# Motor_Driver_SCH_1.net
KiCad netlist of a schematic drawn in Altium Designer
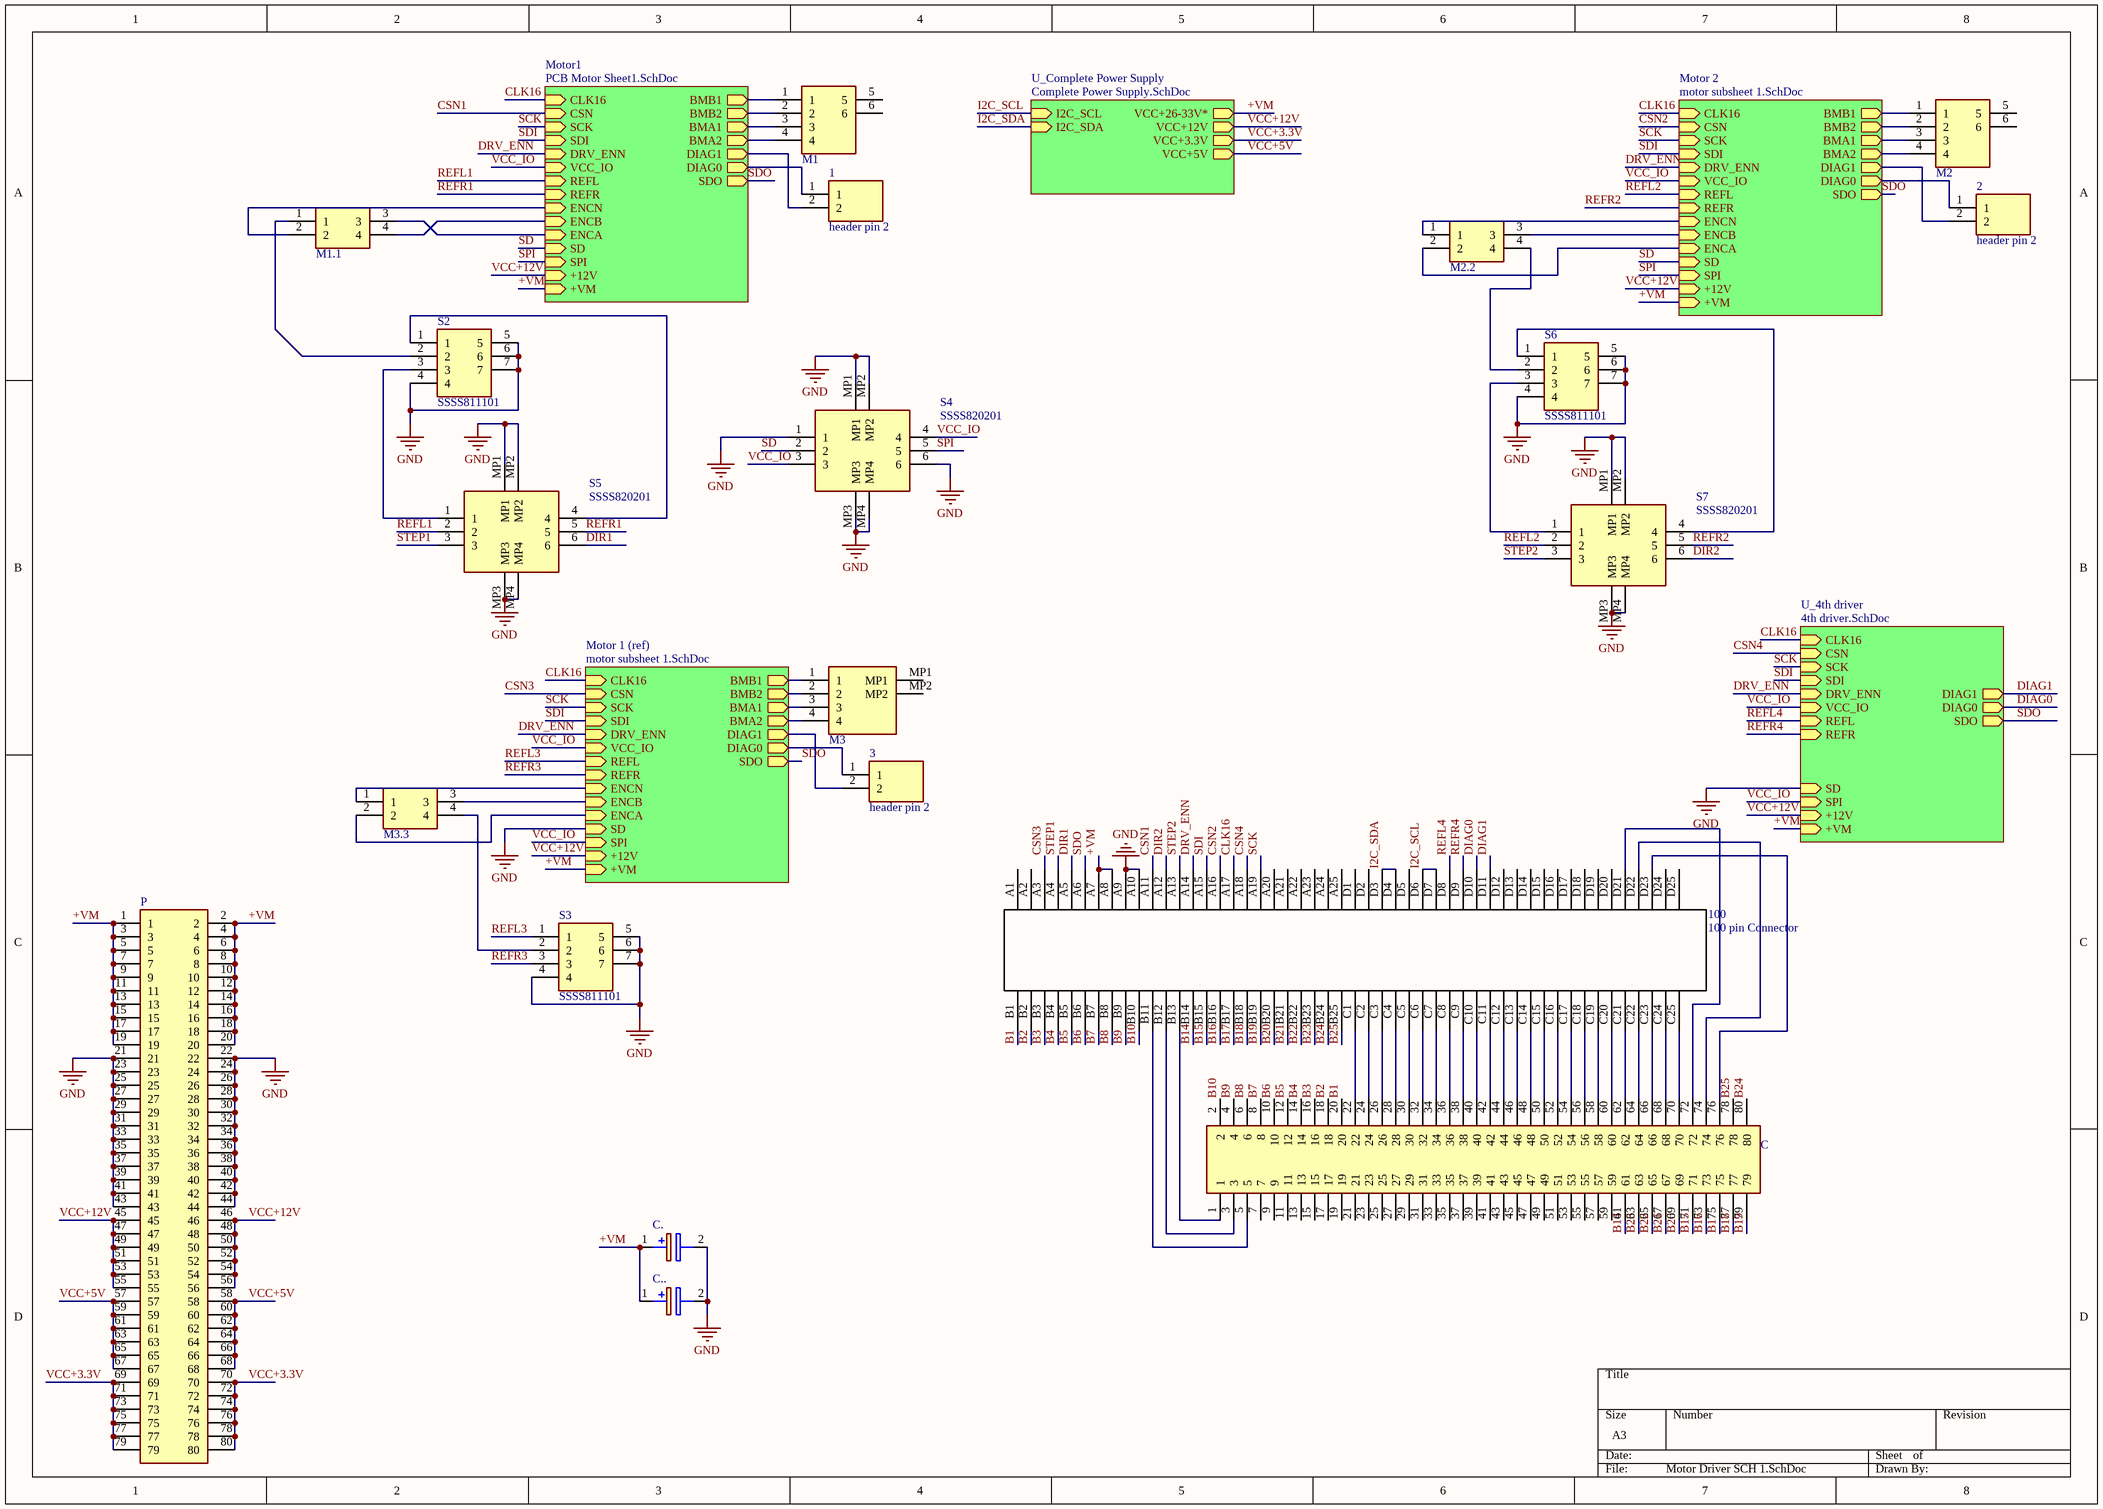
[diagram p0: Motor Driver SCH 1.SchDoc]

(export (version "E")
  (design (tool "Eeschema 10.0.6"))
  (components
    (comp (ref "1")
      (value "header pin 2")
      (footprint "2 pin header")
      (libsource (lib "SamacSys") (part "header pin 2"))
    )
    (comp (ref "2")
      (value "header pin 2")
      (footprint "2 pin header")
      (libsource (lib "SamacSys") (part "header pin 2"))
    )
    (comp (ref "3")
      (value "header pin 2")
      (footprint "2 pin header")
      (libsource (lib "SamacSys") (part "header pin 2"))
    )
    (comp (ref "100")
      (value "100 pin Connector")
      (footprint "SAMTEC_FOLC-125-M1-L-Q-LC")
      (libsource (lib "100 PIN Schlib1") (part "100 pin Connector"))
    )
    (comp (ref "C")
      (value "5-5179180-3")
      (footprint "SamacSys:551791803")
      (description "Connector")
      (fields (field (name "MOUSER PART NUMBER") "571-5-5179180-3"))
      (libsource (lib "") (part "5-5179180-3_1"))
    )
    (comp (ref "C.")
      (value "TPSD476M035R0300V")
      (footprint "SamacSys:CAPPM7344X310N")
      (description "Capacitor Polarised")
      (fields (field (name "MOUSER PART NUMBER") "581-TPSD476M035R300V"))
      (libsource (lib "*") (part "TPSD476M035R0300V"))
    )
    (comp (ref "C..")
      (value "TPSD476M035R0300V")
      (footprint "SamacSys:CAPPM7344X310N")
      (description "Capacitor Polarised")
      (fields (field (name "MOUSER PART NUMBER") "581-TPSD476M035R300V"))
      (libsource (lib "*") (part "TPSD476M035R0300V"))
    )
    (comp (ref "M1")
      (value "1778780")
      (footprint "SamacSys:1778780")
      (description "Connector")
      (fields (field (name "MOUSER PART NUMBER") "651-1778780"))
      (libsource (lib "*") (part "1778780"))
    )
    (comp (ref "M1.1")
      (value "SM04B-XSRS-ETB_LF__SN_")
      (footprint "SamacSys:SM04B-XSRS-ETB_2")
      (description "Connector")
      (fields (field (name "MANUFACTURER_PART_NUMBER") "SM04B-XSRS-ETB(LF)(SN)"))
      (libsource (lib "*") (part "SM04B-XSRS-ETB_LF__SN_"))
    )
    (comp (ref "M2")
      (value "1778780")
      (footprint "SamacSys:1778780")
      (description "Connector")
      (fields (field (name "MOUSER PART NUMBER") "651-1778780"))
      (libsource (lib "*") (part "1778780"))
    )
    (comp (ref "M2.2")
      (value "SM04B-XSRS-ETB_LF__SN_")
      (footprint "SamacSys:SM04B-XSRS-ETB_2")
      (description "Connector")
      (fields (field (name "MANUFACTURER_PART_NUMBER") "SM04B-XSRS-ETB(LF)(SN)"))
      (libsource (lib "*") (part "SM04B-XSRS-ETB_LF__SN_"))
    )
    (comp (ref "M3")
      (value "BM04B-ACHSS-A-GAN-TF_LF__SN_")
      (footprint "SamacSys:BM04BACHSSAGANTFLFSN")
      (description "Connector")
      (fields (field (name "MANUFACTURER_PART_NUMBER") "BM04B-ACHSS-A-GAN-TF(LF)(SN)"))
      (libsource (lib "*") (part "BM04B-ACHSS-A-GAN-TF_LF__SN_"))
    )
    (comp (ref "M3.3")
      (value "SM04B-XSRS-ETB_LF__SN_")
      (footprint "SamacSys:SM04B-XSRS-ETB_2")
      (description "Connector")
      (fields (field (name "MANUFACTURER_PART_NUMBER") "SM04B-XSRS-ETB(LF)(SN)"))
      (libsource (lib "*") (part "SM04B-XSRS-ETB_LF__SN_"))
    )
    (comp (ref "P")
      (value "5-5179180-3")
      (footprint "SamacSys:551791803")
      (description "Connector")
      (fields (field (name "MOUSER PART NUMBER") "571-5-5179180-3"))
      (libsource (lib "*") (part "5-5179180-3"))
    )
    (comp (ref "S2")
      (value "SSSS811101")
      (footprint "SamacSys:SSSS811101")
      (description "Switch")
      (fields (field (name "MOUSER PART NUMBER") "688-SSSS811101"))
      (libsource (lib "*") (part "SSSS811101"))
    )
    (comp (ref "S3")
      (value "SSSS811101")
      (footprint "SamacSys:SSSS811101")
      (description "Switch")
      (fields (field (name "MOUSER PART NUMBER") "688-SSSS811101"))
      (libsource (lib "*") (part "SSSS811101"))
    )
    (comp (ref "S4")
      (value "SSSS820201")
      (footprint "SamacSys:SSSS820201")
      (description "Switch")
      (fields (field (name "MOUSER PART NUMBER") "688-SSSS820201"))
      (libsource (lib "*") (part "SSSS820201"))
    )
    (comp (ref "S5")
      (value "SSSS820201")
      (footprint "SamacSys:SSSS820201")
      (description "Switch")
      (fields (field (name "MOUSER PART NUMBER") "688-SSSS820201"))
      (libsource (lib "*") (part "SSSS820201"))
    )
    (comp (ref "S6")
      (value "SSSS811101")
      (footprint "SamacSys:SSSS811101")
      (description "Switch")
      (fields (field (name "MOUSER PART NUMBER") "688-SSSS811101"))
      (libsource (lib "*") (part "SSSS811101"))
    )
    (comp (ref "S7")
      (value "SSSS820201")
      (footprint "SamacSys:SSSS820201")
      (description "Switch")
      (fields (field (name "MOUSER PART NUMBER") "688-SSSS820201"))
      (libsource (lib "*") (part "SSSS820201"))
    )
  )
  (nets
    (net (code "1") (name "/+VM") (class "Default")
      (node (ref "100") (pin "A7") (pinfunction "32_A7") (pintype "passive"))
      (node (ref "100") (pin "A8") (pinfunction "33_A8") (pintype "passive"))
      (node (ref "C.") (pin "1") (pinfunction "+_1") (pintype "passive"))
      (node (ref "C..") (pin "1") (pinfunction "+_1") (pintype "passive"))
      (node (ref "P") (pin "1") (pinfunction "1_1") (pintype "passive"))
      (node (ref "P") (pin "10") (pinfunction "10_10") (pintype "passive"))
      (node (ref "P") (pin "11") (pinfunction "11_11") (pintype "passive"))
      (node (ref "P") (pin "12") (pinfunction "12_12") (pintype "passive"))
      (node (ref "P") (pin "13") (pinfunction "13_13") (pintype "passive"))
      (node (ref "P") (pin "14") (pinfunction "14_14") (pintype "passive"))
      (node (ref "P") (pin "15") (pinfunction "15_15") (pintype "passive"))
      (node (ref "P") (pin "16") (pinfunction "16_16") (pintype "passive"))
      (node (ref "P") (pin "17") (pinfunction "17_17") (pintype "passive"))
      (node (ref "P") (pin "18") (pinfunction "18_18") (pintype "passive"))
      (node (ref "P") (pin "19") (pinfunction "19_19") (pintype "passive"))
      (node (ref "P") (pin "2") (pinfunction "2_2") (pintype "passive"))
      (node (ref "P") (pin "20") (pinfunction "20_20") (pintype "passive"))
      (node (ref "P") (pin "3") (pinfunction "3_3") (pintype "passive"))
      (node (ref "P") (pin "4") (pinfunction "4_4") (pintype "passive"))
      (node (ref "P") (pin "5") (pinfunction "5_5") (pintype "passive"))
      (node (ref "P") (pin "6") (pinfunction "6_6") (pintype "passive"))
      (node (ref "P") (pin "7") (pinfunction "7_7") (pintype "passive"))
      (node (ref "P") (pin "8") (pinfunction "8_8") (pintype "passive"))
      (node (ref "P") (pin "9") (pinfunction "9_9") (pintype "passive"))
    )
    (net (code "2") (name "/B1") (class "Default")
      (node (ref "100") (pin "B1") (pinfunction "51_B1") (pintype "passive"))
      (node (ref "C") (pin "20") (pinfunction "20_20") (pintype "passive"))
    )
    (net (code "3") (name "/B2") (class "Default")
      (node (ref "100") (pin "B2") (pinfunction "52_B2") (pintype "passive"))
      (node (ref "C") (pin "18") (pinfunction "18_18") (pintype "passive"))
    )
    (net (code "4") (name "/B3") (class "Default")
      (node (ref "100") (pin "B3") (pinfunction "53_B3") (pintype "passive"))
      (node (ref "C") (pin "16") (pinfunction "16_16") (pintype "passive"))
    )
    (net (code "5") (name "/B4") (class "Default")
      (node (ref "100") (pin "B4") (pinfunction "54_B4") (pintype "passive"))
      (node (ref "C") (pin "14") (pinfunction "14_14") (pintype "passive"))
    )
    (net (code "6") (name "/B5") (class "Default")
      (node (ref "100") (pin "B5") (pinfunction "55_B5") (pintype "passive"))
      (node (ref "C") (pin "12") (pinfunction "12_12") (pintype "passive"))
    )
    (net (code "7") (name "/B6") (class "Default")
      (node (ref "100") (pin "B6") (pinfunction "56_B6") (pintype "passive"))
      (node (ref "C") (pin "10") (pinfunction "10_10") (pintype "passive"))
    )
    (net (code "8") (name "/B7") (class "Default")
      (node (ref "100") (pin "B7") (pinfunction "57_B7") (pintype "passive"))
      (node (ref "C") (pin "8") (pinfunction "8_8") (pintype "passive"))
    )
    (net (code "9") (name "/B8") (class "Default")
      (node (ref "100") (pin "B8") (pinfunction "58_B8") (pintype "passive"))
      (node (ref "C") (pin "6") (pinfunction "6_6") (pintype "passive"))
    )
    (net (code "10") (name "/B9") (class "Default")
      (node (ref "100") (pin "B9") (pinfunction "59_B9") (pintype "passive"))
      (node (ref "C") (pin "4") (pinfunction "4_4") (pintype "passive"))
    )
    (net (code "11") (name "/B10") (class "Default")
      (node (ref "100") (pin "B10") (pinfunction "60_B10") (pintype "passive"))
      (node (ref "C") (pin "2") (pinfunction "2_2") (pintype "passive"))
    )
    (net (code "12") (name "/B14") (class "Default")
      (node (ref "100") (pin "B14") (pinfunction "64_B14") (pintype "passive"))
      (node (ref "C") (pin "61") (pinfunction "61_61") (pintype "passive"))
    )
    (net (code "13") (name "/B15") (class "Default")
      (node (ref "100") (pin "B15") (pinfunction "65_B15") (pintype "passive"))
      (node (ref "C") (pin "71") (pinfunction "71_71") (pintype "passive"))
    )
    (net (code "14") (name "/B16") (class "Default")
      (node (ref "100") (pin "B16") (pinfunction "66_B16") (pintype "passive"))
      (node (ref "C") (pin "73") (pinfunction "73_73") (pintype "passive"))
    )
    (net (code "15") (name "/B17") (class "Default")
      (node (ref "100") (pin "B17") (pinfunction "67_B17") (pintype "passive"))
      (node (ref "C") (pin "75") (pinfunction "75_75") (pintype "passive"))
    )
    (net (code "16") (name "/B18") (class "Default")
      (node (ref "100") (pin "B18") (pinfunction "68_B18") (pintype "passive"))
      (node (ref "C") (pin "77") (pinfunction "77_77") (pintype "passive"))
    )
    (net (code "17") (name "/B19") (class "Default")
      (node (ref "100") (pin "B19") (pinfunction "69_B19") (pintype "passive"))
      (node (ref "C") (pin "79") (pinfunction "79_79") (pintype "passive"))
    )
    (net (code "18") (name "/B20") (class "Default")
      (node (ref "100") (pin "B20") (pinfunction "70_B20") (pintype "passive"))
      (node (ref "C") (pin "69") (pinfunction "69_69") (pintype "passive"))
    )
    (net (code "19") (name "/B21") (class "Default")
      (node (ref "100") (pin "B21") (pinfunction "71_B21") (pintype "passive"))
      (node (ref "C") (pin "67") (pinfunction "67_67") (pintype "passive"))
    )
    (net (code "20") (name "/B22") (class "Default")
      (node (ref "100") (pin "B22") (pinfunction "72_B22") (pintype "passive"))
      (node (ref "C") (pin "65") (pinfunction "65_65") (pintype "passive"))
    )
    (net (code "21") (name "/B23") (class "Default")
      (node (ref "100") (pin "B23") (pinfunction "73_B23") (pintype "passive"))
      (node (ref "C") (pin "63") (pinfunction "63_63") (pintype "passive"))
    )
    (net (code "22") (name "/B24") (class "Default")
      (node (ref "100") (pin "B24") (pinfunction "74_B24") (pintype "passive"))
      (node (ref "C") (pin "80") (pinfunction "80_80") (pintype "passive"))
    )
    (net (code "23") (name "/B25") (class "Default")
      (node (ref "100") (pin "B25") (pinfunction "75_B25") (pintype "passive"))
      (node (ref "C") (pin "78") (pinfunction "78_78") (pintype "passive"))
    )
    (net (code "24") (name "/BMA1") (class "Default")
      (node (ref "M2") (pin "3") (pinfunction "3_3") (pintype "passive"))
    )
    (net (code "25") (name "/BMA1_1") (class "Default")
      (node (ref "M1") (pin "3") (pinfunction "3_3") (pintype "passive"))
    )
    (net (code "26") (name "/BMA1_2") (class "Default")
      (node (ref "M3") (pin "3") (pinfunction "3_3") (pintype "passive"))
    )
    (net (code "27") (name "/BMA2") (class "Default")
      (node (ref "M2") (pin "4") (pinfunction "4_4") (pintype "passive"))
    )
    (net (code "28") (name "/BMA2_1") (class "Default")
      (node (ref "M1") (pin "4") (pinfunction "4_4") (pintype "passive"))
    )
    (net (code "29") (name "/BMA2_2") (class "Default")
      (node (ref "M3") (pin "4") (pinfunction "4_4") (pintype "passive"))
    )
    (net (code "30") (name "/BMB1") (class "Default")
      (node (ref "M2") (pin "1") (pinfunction "1_1") (pintype "passive"))
    )
    (net (code "31") (name "/BMB1_1") (class "Default")
      (node (ref "M1") (pin "1") (pinfunction "1_1") (pintype "passive"))
    )
    (net (code "32") (name "/BMB1_2") (class "Default")
      (node (ref "M3") (pin "1") (pinfunction "1_1") (pintype "passive"))
    )
    (net (code "33") (name "/BMB2") (class "Default")
      (node (ref "M2") (pin "2") (pinfunction "2_2") (pintype "passive"))
    )
    (net (code "34") (name "/BMB2_1") (class "Default")
      (node (ref "M1") (pin "2") (pinfunction "2_2") (pintype "passive"))
    )
    (net (code "35") (name "/BMB2_2") (class "Default")
      (node (ref "M3") (pin "2") (pinfunction "2_2") (pintype "passive"))
    )
    (net (code "36") (name "/CLK16") (class "Default")
      (node (ref "100") (pin "A17") (pinfunction "42_A17") (pintype "passive"))
    )
    (net (code "37") (name "/CSN1") (class "Default")
      (node (ref "100") (pin "A11") (pinfunction "36_A11") (pintype "passive"))
    )
    (net (code "38") (name "/CSN2") (class "Default")
      (node (ref "100") (pin "A16") (pinfunction "41_A16") (pintype "passive"))
    )
    (net (code "39") (name "/CSN3") (class "Default")
      (node (ref "100") (pin "A3") (pinfunction "28_A3") (pintype "passive"))
    )
    (net (code "40") (name "/CSN4") (class "Default")
      (node (ref "100") (pin "A18") (pinfunction "43_A18") (pintype "passive"))
    )
    (net (code "41") (name "/DIAG0") (class "Default")
      (node (ref "100") (pin "D10") (pinfunction "110_D10") (pintype "passive"))
    )
    (net (code "42") (name "/DIAG0_1") (class "Default")
      (node (ref "1") (pin "1") (pinfunction "1_1") (pintype "passive"))
    )
    (net (code "43") (name "/DIAG0_2") (class "Default")
      (node (ref "3") (pin "1") (pinfunction "1_1") (pintype "passive"))
    )
    (net (code "44") (name "/DIAG0_3") (class "Default")
      (node (ref "2") (pin "1") (pinfunction "1_1") (pintype "passive"))
    )
    (net (code "45") (name "/DIAG1") (class "Default")
      (node (ref "100") (pin "D11") (pinfunction "111_D11") (pintype "passive"))
    )
    (net (code "46") (name "/DIAG1_1") (class "Default")
      (node (ref "1") (pin "2") (pinfunction "2_2") (pintype "passive"))
    )
    (net (code "47") (name "/DIAG1_2") (class "Default")
      (node (ref "3") (pin "2") (pinfunction "2_2") (pintype "passive"))
    )
    (net (code "48") (name "/DIAG1_3") (class "Default")
      (node (ref "2") (pin "2") (pinfunction "2_2") (pintype "passive"))
    )
    (net (code "49") (name "/DIR1") (class "Default")
      (node (ref "100") (pin "A5") (pinfunction "30_A5") (pintype "passive"))
      (node (ref "S5") (pin "6") (pinfunction "6_6") (pintype "passive"))
    )
    (net (code "50") (name "/DIR2") (class "Default")
      (node (ref "100") (pin "A12") (pinfunction "37_A12") (pintype "passive"))
      (node (ref "S7") (pin "6") (pinfunction "6_6") (pintype "passive"))
    )
    (net (code "51") (name "/DRV_ENN") (class "Default")
      (node (ref "100") (pin "A14") (pinfunction "39_A14") (pintype "passive"))
    )
    (net (code "52") (name "/ENCA") (class "Default")
      (node (ref "M2.2") (pin "2") (pinfunction "2_2") (pintype "passive"))
    )
    (net (code "53") (name "/ENCA_1") (class "Default")
      (node (ref "M3.3") (pin "2") (pinfunction "2_2") (pintype "passive"))
    )
    (net (code "54") (name "/ENCA_2") (class "Default")
      (node (ref "M1.1") (pin "3") (pinfunction "3_3") (pintype "passive"))
    )
    (net (code "55") (name "/ENCB") (class "Default")
      (node (ref "M2.2") (pin "3") (pinfunction "3_3") (pintype "passive"))
    )
    (net (code "56") (name "/ENCB_1") (class "Default")
      (node (ref "M3.3") (pin "3") (pinfunction "3_3") (pintype "passive"))
    )
    (net (code "57") (name "/ENCB_2") (class "Default")
      (node (ref "M1.1") (pin "4") (pinfunction "4_4") (pintype "passive"))
    )
    (net (code "58") (name "/ENCN") (class "Default")
      (node (ref "M2.2") (pin "1") (pinfunction "1_1") (pintype "passive"))
    )
    (net (code "59") (name "/ENCN_1") (class "Default")
      (node (ref "M3.3") (pin "1") (pinfunction "1_1") (pintype "passive"))
    )
    (net (code "60") (name "/ENCN_2") (class "Default")
      (node (ref "M1.1") (pin "2") (pinfunction "2_2") (pintype "passive"))
    )
    (net (code "61") (name "/I2C_SCL") (class "Default")
      (node (ref "100") (pin "D6") (pinfunction "106_D6") (pintype "passive"))
      (node (ref "100") (pin "D7") (pinfunction "107_D7") (pintype "passive"))
    )
    (net (code "62") (name "/I2C_SDA") (class "Default")
      (node (ref "100") (pin "D3") (pinfunction "103_D3") (pintype "passive"))
      (node (ref "100") (pin "D4") (pinfunction "104_D4") (pintype "passive"))
    )
    (net (code "63") (name "/REFL1") (class "Default")
      (node (ref "S5") (pin "2") (pinfunction "2_2") (pintype "passive"))
    )
    (net (code "64") (name "/REFL2") (class "Default")
      (node (ref "S7") (pin "2") (pinfunction "2_2") (pintype "passive"))
    )
    (net (code "65") (name "/REFL3") (class "Default")
      (node (ref "S3") (pin "1") (pinfunction "1_1") (pintype "passive"))
    )
    (net (code "66") (name "/REFL4") (class "Default")
      (node (ref "100") (pin "D8") (pinfunction "108_D8") (pintype "passive"))
    )
    (net (code "67") (name "/REFR1") (class "Default")
      (node (ref "S5") (pin "5") (pinfunction "5_5") (pintype "passive"))
    )
    (net (code "68") (name "/REFR2") (class "Default")
      (node (ref "S7") (pin "5") (pinfunction "5_5") (pintype "passive"))
    )
    (net (code "69") (name "/REFR3") (class "Default")
      (node (ref "S3") (pin "3") (pinfunction "3_3") (pintype "passive"))
    )
    (net (code "70") (name "/REFR4") (class "Default")
      (node (ref "100") (pin "D9") (pinfunction "109_D9") (pintype "passive"))
    )
    (net (code "71") (name "/SCK") (class "Default")
      (node (ref "100") (pin "A19") (pinfunction "44_A19") (pintype "passive"))
    )
    (net (code "72") (name "/SD") (class "Default")
      (node (ref "S4") (pin "2") (pinfunction "2_2") (pintype "passive"))
    )
    (net (code "73") (name "/SDI") (class "Default")
      (node (ref "100") (pin "A15") (pinfunction "40_A15") (pintype "passive"))
    )
    (net (code "74") (name "/SDO") (class "Default")
      (node (ref "100") (pin "A6") (pinfunction "31_A6") (pintype "passive"))
    )
    (net (code "75") (name "/SPI") (class "Default")
      (node (ref "S4") (pin "5") (pinfunction "5_5") (pintype "passive"))
    )
    (net (code "76") (name "/STEP1") (class "Default")
      (node (ref "100") (pin "A4") (pinfunction "29_A4") (pintype "passive"))
      (node (ref "S5") (pin "3") (pinfunction "3_3") (pintype "passive"))
    )
    (net (code "77") (name "/STEP2") (class "Default")
      (node (ref "100") (pin "A13") (pinfunction "38_A13") (pintype "passive"))
      (node (ref "S7") (pin "3") (pinfunction "3_3") (pintype "passive"))
    )
    (net (code "78") (name "/VCC+3.3V") (class "Default")
      (node (ref "P") (pin "69") (pinfunction "69_69") (pintype "passive"))
      (node (ref "P") (pin "70") (pinfunction "70_70") (pintype "passive"))
      (node (ref "P") (pin "71") (pinfunction "71_71") (pintype "passive"))
      (node (ref "P") (pin "72") (pinfunction "72_72") (pintype "passive"))
      (node (ref "P") (pin "73") (pinfunction "73_73") (pintype "passive"))
      (node (ref "P") (pin "74") (pinfunction "74_74") (pintype "passive"))
      (node (ref "P") (pin "75") (pinfunction "75_75") (pintype "passive"))
      (node (ref "P") (pin "76") (pinfunction "76_76") (pintype "passive"))
      (node (ref "P") (pin "77") (pinfunction "77_77") (pintype "passive"))
      (node (ref "P") (pin "78") (pinfunction "78_78") (pintype "passive"))
      (node (ref "P") (pin "79") (pinfunction "79_79") (pintype "passive"))
      (node (ref "P") (pin "80") (pinfunction "80_80") (pintype "passive"))
    )
    (net (code "79") (name "/VCC+5V") (class "Default")
      (node (ref "P") (pin "57") (pinfunction "57_57") (pintype "passive"))
      (node (ref "P") (pin "58") (pinfunction "58_58") (pintype "passive"))
      (node (ref "P") (pin "59") (pinfunction "59_59") (pintype "passive"))
      (node (ref "P") (pin "60") (pinfunction "60_60") (pintype "passive"))
      (node (ref "P") (pin "61") (pinfunction "61_61") (pintype "passive"))
      (node (ref "P") (pin "62") (pinfunction "62_62") (pintype "passive"))
      (node (ref "P") (pin "63") (pinfunction "63_63") (pintype "passive"))
      (node (ref "P") (pin "64") (pinfunction "64_64") (pintype "passive"))
      (node (ref "P") (pin "65") (pinfunction "65_65") (pintype "passive"))
      (node (ref "P") (pin "66") (pinfunction "66_66") (pintype "passive"))
      (node (ref "P") (pin "67") (pinfunction "67_67") (pintype "passive"))
      (node (ref "P") (pin "68") (pinfunction "68_68") (pintype "passive"))
    )
    (net (code "80") (name "/VCC+12V") (class "Default")
      (node (ref "P") (pin "45") (pinfunction "45_45") (pintype "passive"))
      (node (ref "P") (pin "46") (pinfunction "46_46") (pintype "passive"))
      (node (ref "P") (pin "47") (pinfunction "47_47") (pintype "passive"))
      (node (ref "P") (pin "48") (pinfunction "48_48") (pintype "passive"))
      (node (ref "P") (pin "49") (pinfunction "49_49") (pintype "passive"))
      (node (ref "P") (pin "50") (pinfunction "50_50") (pintype "passive"))
      (node (ref "P") (pin "51") (pinfunction "51_51") (pintype "passive"))
      (node (ref "P") (pin "52") (pinfunction "52_52") (pintype "passive"))
      (node (ref "P") (pin "53") (pinfunction "53_53") (pintype "passive"))
      (node (ref "P") (pin "54") (pinfunction "54_54") (pintype "passive"))
      (node (ref "P") (pin "55") (pinfunction "55_55") (pintype "passive"))
      (node (ref "P") (pin "56") (pinfunction "56_56") (pintype "passive"))
    )
    (net (code "81") (name "/VCC_IO") (class "Default")
      (node (ref "S4") (pin "3") (pinfunction "3_3") (pintype "passive"))
      (node (ref "S4") (pin "4") (pinfunction "4_4") (pintype "passive"))
    )
    (net (code "82") (name "GND") (class "Default")
      (node (ref "100") (pin "A10") (pinfunction "35_A10") (pintype "passive"))
      (node (ref "100") (pin "A9") (pinfunction "34_A9") (pintype "passive"))
      (node (ref "C.") (pin "2") (pinfunction "-_2") (pintype "passive"))
      (node (ref "C..") (pin "2") (pinfunction "-_2") (pintype "passive"))
      (node (ref "P") (pin "21") (pinfunction "21_21") (pintype "passive"))
      (node (ref "P") (pin "22") (pinfunction "22_22") (pintype "passive"))
      (node (ref "P") (pin "23") (pinfunction "23_23") (pintype "passive"))
      (node (ref "P") (pin "24") (pinfunction "24_24") (pintype "passive"))
      (node (ref "P") (pin "25") (pinfunction "25_25") (pintype "passive"))
      (node (ref "P") (pin "26") (pinfunction "26_26") (pintype "passive"))
      (node (ref "P") (pin "27") (pinfunction "27_27") (pintype "passive"))
      (node (ref "P") (pin "28") (pinfunction "28_28") (pintype "passive"))
      (node (ref "P") (pin "29") (pinfunction "29_29") (pintype "passive"))
      (node (ref "P") (pin "30") (pinfunction "30_30") (pintype "passive"))
      (node (ref "P") (pin "31") (pinfunction "31_31") (pintype "passive"))
      (node (ref "P") (pin "32") (pinfunction "32_32") (pintype "passive"))
      (node (ref "P") (pin "33") (pinfunction "33_33") (pintype "passive"))
      (node (ref "P") (pin "34") (pinfunction "34_34") (pintype "passive"))
      (node (ref "P") (pin "35") (pinfunction "35_35") (pintype "passive"))
      (node (ref "P") (pin "36") (pinfunction "36_36") (pintype "passive"))
      (node (ref "P") (pin "37") (pinfunction "37_37") (pintype "passive"))
      (node (ref "P") (pin "38") (pinfunction "38_38") (pintype "passive"))
      (node (ref "P") (pin "39") (pinfunction "39_39") (pintype "passive"))
      (node (ref "P") (pin "40") (pinfunction "40_40") (pintype "passive"))
      (node (ref "P") (pin "41") (pinfunction "41_41") (pintype "passive"))
      (node (ref "P") (pin "42") (pinfunction "42_42") (pintype "passive"))
      (node (ref "P") (pin "43") (pinfunction "43_43") (pintype "passive"))
      (node (ref "P") (pin "44") (pinfunction "44_44") (pintype "passive"))
      (node (ref "S2") (pin "4") (pinfunction "4_4") (pintype "passive"))
      (node (ref "S2") (pin "5") (pinfunction "5_5") (pintype "passive"))
      (node (ref "S2") (pin "6") (pinfunction "6_6") (pintype "passive"))
      (node (ref "S2") (pin "7") (pinfunction "7_7") (pintype "passive"))
      (node (ref "S3") (pin "4") (pinfunction "4_4") (pintype "passive"))
      (node (ref "S3") (pin "5") (pinfunction "5_5") (pintype "passive"))
      (node (ref "S3") (pin "6") (pinfunction "6_6") (pintype "passive"))
      (node (ref "S3") (pin "7") (pinfunction "7_7") (pintype "passive"))
      (node (ref "S4") (pin "1") (pinfunction "1_1") (pintype "passive"))
      (node (ref "S4") (pin "6") (pinfunction "6_6") (pintype "passive"))
      (node (ref "S4") (pin "MP1") (pinfunction "MP1_MP1") (pintype "passive"))
      (node (ref "S4") (pin "MP2") (pinfunction "MP2_MP2") (pintype "passive"))
      (node (ref "S4") (pin "MP3") (pinfunction "MP3_MP3") (pintype "passive"))
      (node (ref "S4") (pin "MP4") (pinfunction "MP4_MP4") (pintype "passive"))
      (node (ref "S5") (pin "MP1") (pinfunction "MP1_MP1") (pintype "passive"))
      (node (ref "S5") (pin "MP2") (pinfunction "MP2_MP2") (pintype "passive"))
      (node (ref "S5") (pin "MP3") (pinfunction "MP3_MP3") (pintype "passive"))
      (node (ref "S5") (pin "MP4") (pinfunction "MP4_MP4") (pintype "passive"))
      (node (ref "S6") (pin "4") (pinfunction "4_4") (pintype "passive"))
      (node (ref "S6") (pin "5") (pinfunction "5_5") (pintype "passive"))
      (node (ref "S6") (pin "6") (pinfunction "6_6") (pintype "passive"))
      (node (ref "S6") (pin "7") (pinfunction "7_7") (pintype "passive"))
      (node (ref "S7") (pin "MP1") (pinfunction "MP1_MP1") (pintype "passive"))
      (node (ref "S7") (pin "MP2") (pinfunction "MP2_MP2") (pintype "passive"))
      (node (ref "S7") (pin "MP3") (pinfunction "MP3_MP3") (pintype "passive"))
      (node (ref "S7") (pin "MP4") (pinfunction "MP4_MP4") (pintype "passive"))
    )
    (net (code "83") (name "Net-(100-61)") (class "Default")
      (node (ref "100") (pin "B11") (pinfunction "61_B11") (pintype "passive"))
      (node (ref "C") (pin "5") (pinfunction "5_5") (pintype "passive"))
    )
    (net (code "84") (name "Net-(100-62)") (class "Default")
      (node (ref "100") (pin "B12") (pinfunction "62_B12") (pintype "passive"))
      (node (ref "C") (pin "3") (pinfunction "3_3") (pintype "passive"))
    )
    (net (code "85") (name "Net-(100-63)") (class "Default")
      (node (ref "100") (pin "B13") (pinfunction "63_B13") (pintype "passive"))
      (node (ref "C") (pin "1") (pinfunction "1_1") (pintype "passive"))
    )
    (net (code "86") (name "Net-(100-76)") (class "Default")
      (node (ref "100") (pin "C1") (pinfunction "76_C1") (pintype "passive"))
      (node (ref "C") (pin "22") (pinfunction "22_22") (pintype "passive"))
    )
    (net (code "87") (name "Net-(100-77)") (class "Default")
      (node (ref "100") (pin "C2") (pinfunction "77_C2") (pintype "passive"))
      (node (ref "C") (pin "24") (pinfunction "24_24") (pintype "passive"))
    )
    (net (code "88") (name "Net-(100-78)") (class "Default")
      (node (ref "100") (pin "C3") (pinfunction "78_C3") (pintype "passive"))
      (node (ref "C") (pin "26") (pinfunction "26_26") (pintype "passive"))
    )
    (net (code "89") (name "Net-(100-79)") (class "Default")
      (node (ref "100") (pin "C4") (pinfunction "79_C4") (pintype "passive"))
      (node (ref "C") (pin "28") (pinfunction "28_28") (pintype "passive"))
    )
    (net (code "90") (name "Net-(100-80)") (class "Default")
      (node (ref "100") (pin "C5") (pinfunction "80_C5") (pintype "passive"))
      (node (ref "C") (pin "30") (pinfunction "30_30") (pintype "passive"))
    )
    (net (code "91") (name "Net-(100-81)") (class "Default")
      (node (ref "100") (pin "C6") (pinfunction "81_C6") (pintype "passive"))
      (node (ref "C") (pin "32") (pinfunction "32_32") (pintype "passive"))
    )
    (net (code "92") (name "Net-(100-82)") (class "Default")
      (node (ref "100") (pin "C7") (pinfunction "82_C7") (pintype "passive"))
      (node (ref "C") (pin "34") (pinfunction "34_34") (pintype "passive"))
    )
    (net (code "93") (name "Net-(100-83)") (class "Default")
      (node (ref "100") (pin "C8") (pinfunction "83_C8") (pintype "passive"))
      (node (ref "C") (pin "36") (pinfunction "36_36") (pintype "passive"))
    )
    (net (code "94") (name "Net-(100-84)") (class "Default")
      (node (ref "100") (pin "C9") (pinfunction "84_C9") (pintype "passive"))
      (node (ref "C") (pin "38") (pinfunction "38_38") (pintype "passive"))
    )
    (net (code "95") (name "Net-(100-85)") (class "Default")
      (node (ref "100") (pin "C10") (pinfunction "85_C10") (pintype "passive"))
      (node (ref "C") (pin "40") (pinfunction "40_40") (pintype "passive"))
    )
    (net (code "96") (name "Net-(100-86)") (class "Default")
      (node (ref "100") (pin "C11") (pinfunction "86_C11") (pintype "passive"))
      (node (ref "C") (pin "42") (pinfunction "42_42") (pintype "passive"))
    )
    (net (code "97") (name "Net-(100-87)") (class "Default")
      (node (ref "100") (pin "C12") (pinfunction "87_C12") (pintype "passive"))
      (node (ref "C") (pin "44") (pinfunction "44_44") (pintype "passive"))
    )
    (net (code "98") (name "Net-(100-88)") (class "Default")
      (node (ref "100") (pin "C13") (pinfunction "88_C13") (pintype "passive"))
      (node (ref "C") (pin "46") (pinfunction "46_46") (pintype "passive"))
    )
    (net (code "99") (name "Net-(100-89)") (class "Default")
      (node (ref "100") (pin "C14") (pinfunction "89_C14") (pintype "passive"))
      (node (ref "C") (pin "48") (pinfunction "48_48") (pintype "passive"))
    )
    (net (code "100") (name "Net-(100-90)") (class "Default")
      (node (ref "100") (pin "C15") (pinfunction "90_C15") (pintype "passive"))
      (node (ref "C") (pin "50") (pinfunction "50_50") (pintype "passive"))
    )
    (net (code "101") (name "Net-(100-91)") (class "Default")
      (node (ref "100") (pin "C16") (pinfunction "91_C16") (pintype "passive"))
      (node (ref "C") (pin "52") (pinfunction "52_52") (pintype "passive"))
    )
    (net (code "102") (name "Net-(100-92)") (class "Default")
      (node (ref "100") (pin "C17") (pinfunction "92_C17") (pintype "passive"))
      (node (ref "C") (pin "54") (pinfunction "54_54") (pintype "passive"))
    )
    (net (code "103") (name "Net-(100-93)") (class "Default")
      (node (ref "100") (pin "C18") (pinfunction "93_C18") (pintype "passive"))
      (node (ref "C") (pin "56") (pinfunction "56_56") (pintype "passive"))
    )
    (net (code "104") (name "Net-(100-94)") (class "Default")
      (node (ref "100") (pin "C19") (pinfunction "94_C19") (pintype "passive"))
      (node (ref "C") (pin "58") (pinfunction "58_58") (pintype "passive"))
    )
    (net (code "105") (name "Net-(100-95)") (class "Default")
      (node (ref "100") (pin "C20") (pinfunction "95_C20") (pintype "passive"))
      (node (ref "C") (pin "60") (pinfunction "60_60") (pintype "passive"))
    )
    (net (code "106") (name "Net-(100-96)") (class "Default")
      (node (ref "100") (pin "C21") (pinfunction "96_C21") (pintype "passive"))
      (node (ref "C") (pin "62") (pinfunction "62_62") (pintype "passive"))
    )
    (net (code "107") (name "Net-(100-97)") (class "Default")
      (node (ref "100") (pin "C22") (pinfunction "97_C22") (pintype "passive"))
      (node (ref "C") (pin "64") (pinfunction "64_64") (pintype "passive"))
    )
    (net (code "108") (name "Net-(100-98)") (class "Default")
      (node (ref "100") (pin "C23") (pinfunction "98_C23") (pintype "passive"))
      (node (ref "C") (pin "66") (pinfunction "66_66") (pintype "passive"))
    )
    (net (code "109") (name "Net-(100-99)") (class "Default")
      (node (ref "100") (pin "C24") (pinfunction "99_C24") (pintype "passive"))
      (node (ref "C") (pin "68") (pinfunction "68_68") (pintype "passive"))
    )
    (net (code "110") (name "Net-(100-100)") (class "Default")
      (node (ref "100") (pin "C25") (pinfunction "100_C25") (pintype "passive"))
      (node (ref "C") (pin "70") (pinfunction "70_70") (pintype "passive"))
    )
    (net (code "111") (name "Net-(100-121)") (class "Default")
      (node (ref "100") (pin "D21") (pinfunction "121_D21") (pintype "passive"))
      (node (ref "C") (pin "72") (pinfunction "72_72") (pintype "passive"))
    )
    (net (code "112") (name "Net-(100-122)") (class "Default")
      (node (ref "100") (pin "D22") (pinfunction "122_D22") (pintype "passive"))
      (node (ref "C") (pin "74") (pinfunction "74_74") (pintype "passive"))
    )
    (net (code "113") (name "Net-(100-123)") (class "Default")
      (node (ref "100") (pin "D23") (pinfunction "123_D23") (pintype "passive"))
      (node (ref "C") (pin "76") (pinfunction "76_76") (pintype "passive"))
    )
    (net (code "114") (name "Net-(M1.1-Pad1)") (class "Default")
      (node (ref "M1.1") (pin "1") (pinfunction "1_1") (pintype "passive"))
      (node (ref "S2") (pin "2") (pinfunction "2_2") (pintype "passive"))
    )
    (net (code "115") (name "Net-(M2.2-Pad4)") (class "Default")
      (node (ref "M2.2") (pin "4") (pinfunction "4_4") (pintype "passive"))
      (node (ref "S6") (pin "2") (pinfunction "2_2") (pintype "passive"))
    )
    (net (code "116") (name "Net-(M3.3-Pad4)") (class "Default")
      (node (ref "M3.3") (pin "4") (pinfunction "4_4") (pintype "passive"))
      (node (ref "S3") (pin "2") (pinfunction "2_2") (pintype "passive"))
    )
    (net (code "117") (name "Net-(S2-Pad1)") (class "Default")
      (node (ref "S2") (pin "1") (pinfunction "1_1") (pintype "passive"))
      (node (ref "S5") (pin "4") (pinfunction "4_4") (pintype "passive"))
    )
    (net (code "118") (name "Net-(S2-Pad3)") (class "Default")
      (node (ref "S2") (pin "3") (pinfunction "3_3") (pintype "passive"))
      (node (ref "S5") (pin "1") (pinfunction "1_1") (pintype "passive"))
    )
    (net (code "119") (name "Net-(S6-Pad1)") (class "Default")
      (node (ref "S6") (pin "1") (pinfunction "1_1") (pintype "passive"))
      (node (ref "S7") (pin "4") (pinfunction "4_4") (pintype "passive"))
    )
    (net (code "120") (name "Net-(S6-Pad3)") (class "Default")
      (node (ref "S6") (pin "3") (pinfunction "3_3") (pintype "passive"))
      (node (ref "S7") (pin "1") (pinfunction "1_1") (pintype "passive"))
    )
    (net (code "121") (name "unconnected-(100-26-PadA1)") (class "Default")
      (node (ref "100") (pin "A1") (pinfunction "26_A1") (pintype "passive"))
    )
    (net (code "122") (name "unconnected-(100-27-PadA2)") (class "Default")
      (node (ref "100") (pin "A2") (pinfunction "27_A2") (pintype "passive"))
    )
    (net (code "123") (name "unconnected-(100-45-PadA20)") (class "Default")
      (node (ref "100") (pin "A20") (pinfunction "45_A20") (pintype "passive"))
    )
    (net (code "124") (name "unconnected-(100-46-PadA21)") (class "Default")
      (node (ref "100") (pin "A21") (pinfunction "46_A21") (pintype "passive"))
    )
    (net (code "125") (name "unconnected-(100-47-PadA22)") (class "Default")
      (node (ref "100") (pin "A22") (pinfunction "47_A22") (pintype "passive"))
    )
    (net (code "126") (name "unconnected-(100-48-PadA23)") (class "Default")
      (node (ref "100") (pin "A23") (pinfunction "48_A23") (pintype "passive"))
    )
    (net (code "127") (name "unconnected-(100-49-PadA24)") (class "Default")
      (node (ref "100") (pin "A24") (pinfunction "49_A24") (pintype "passive"))
    )
    (net (code "128") (name "unconnected-(100-50-PadA25)") (class "Default")
      (node (ref "100") (pin "A25") (pinfunction "50_A25") (pintype "passive"))
    )
    (net (code "129") (name "unconnected-(100-101-PadD1)") (class "Default")
      (node (ref "100") (pin "D1") (pinfunction "101_D1") (pintype "passive"))
    )
    (net (code "130") (name "unconnected-(100-102-PadD2)") (class "Default")
      (node (ref "100") (pin "D2") (pinfunction "102_D2") (pintype "passive"))
    )
    (net (code "131") (name "unconnected-(100-105-PadD5)") (class "Default")
      (node (ref "100") (pin "D5") (pinfunction "105_D5") (pintype "passive"))
    )
    (net (code "132") (name "unconnected-(100-112-PadD12)") (class "Default")
      (node (ref "100") (pin "D12") (pinfunction "112_D12") (pintype "passive"))
    )
    (net (code "133") (name "unconnected-(100-113-PadD13)") (class "Default")
      (node (ref "100") (pin "D13") (pinfunction "113_D13") (pintype "passive"))
    )
    (net (code "134") (name "unconnected-(100-114-PadD14)") (class "Default")
      (node (ref "100") (pin "D14") (pinfunction "114_D14") (pintype "passive"))
    )
    (net (code "135") (name "unconnected-(100-115-PadD15)") (class "Default")
      (node (ref "100") (pin "D15") (pinfunction "115_D15") (pintype "passive"))
    )
    (net (code "136") (name "unconnected-(100-116-PadD16)") (class "Default")
      (node (ref "100") (pin "D16") (pinfunction "116_D16") (pintype "passive"))
    )
    (net (code "137") (name "unconnected-(100-117-PadD17)") (class "Default")
      (node (ref "100") (pin "D17") (pinfunction "117_D17") (pintype "passive"))
    )
    (net (code "138") (name "unconnected-(100-118-PadD18)") (class "Default")
      (node (ref "100") (pin "D18") (pinfunction "118_D18") (pintype "passive"))
    )
    (net (code "139") (name "unconnected-(100-119-PadD19)") (class "Default")
      (node (ref "100") (pin "D19") (pinfunction "119_D19") (pintype "passive"))
    )
    (net (code "140") (name "unconnected-(100-120-PadD20)") (class "Default")
      (node (ref "100") (pin "D20") (pinfunction "120_D20") (pintype "passive"))
    )
    (net (code "141") (name "unconnected-(100-124-PadD24)") (class "Default")
      (node (ref "100") (pin "D24") (pinfunction "124_D24") (pintype "passive"))
    )
    (net (code "142") (name "unconnected-(100-125-PadD25)") (class "Default")
      (node (ref "100") (pin "D25") (pinfunction "125_D25") (pintype "passive"))
    )
    (net (code "143") (name "unconnected-(C-Pad7)") (class "Default")
      (node (ref "C") (pin "7") (pinfunction "7_7") (pintype "passive"))
    )
    (net (code "144") (name "unconnected-(C-Pad9)") (class "Default")
      (node (ref "C") (pin "9") (pinfunction "9_9") (pintype "passive"))
    )
    (net (code "145") (name "unconnected-(C-Pad11)") (class "Default")
      (node (ref "C") (pin "11") (pinfunction "11_11") (pintype "passive"))
    )
    (net (code "146") (name "unconnected-(C-Pad13)") (class "Default")
      (node (ref "C") (pin "13") (pinfunction "13_13") (pintype "passive"))
    )
    (net (code "147") (name "unconnected-(C-Pad15)") (class "Default")
      (node (ref "C") (pin "15") (pinfunction "15_15") (pintype "passive"))
    )
    (net (code "148") (name "unconnected-(C-Pad17)") (class "Default")
      (node (ref "C") (pin "17") (pinfunction "17_17") (pintype "passive"))
    )
    (net (code "149") (name "unconnected-(C-Pad19)") (class "Default")
      (node (ref "C") (pin "19") (pinfunction "19_19") (pintype "passive"))
    )
    (net (code "150") (name "unconnected-(C-Pad21)") (class "Default")
      (node (ref "C") (pin "21") (pinfunction "21_21") (pintype "passive"))
    )
    (net (code "151") (name "unconnected-(C-Pad23)") (class "Default")
      (node (ref "C") (pin "23") (pinfunction "23_23") (pintype "passive"))
    )
    (net (code "152") (name "unconnected-(C-Pad25)") (class "Default")
      (node (ref "C") (pin "25") (pinfunction "25_25") (pintype "passive"))
    )
    (net (code "153") (name "unconnected-(C-Pad27)") (class "Default")
      (node (ref "C") (pin "27") (pinfunction "27_27") (pintype "passive"))
    )
    (net (code "154") (name "unconnected-(C-Pad29)") (class "Default")
      (node (ref "C") (pin "29") (pinfunction "29_29") (pintype "passive"))
    )
    (net (code "155") (name "unconnected-(C-Pad31)") (class "Default")
      (node (ref "C") (pin "31") (pinfunction "31_31") (pintype "passive"))
    )
    (net (code "156") (name "unconnected-(C-Pad33)") (class "Default")
      (node (ref "C") (pin "33") (pinfunction "33_33") (pintype "passive"))
    )
    (net (code "157") (name "unconnected-(C-Pad35)") (class "Default")
      (node (ref "C") (pin "35") (pinfunction "35_35") (pintype "passive"))
    )
    (net (code "158") (name "unconnected-(C-Pad37)") (class "Default")
      (node (ref "C") (pin "37") (pinfunction "37_37") (pintype "passive"))
    )
    (net (code "159") (name "unconnected-(C-Pad39)") (class "Default")
      (node (ref "C") (pin "39") (pinfunction "39_39") (pintype "passive"))
    )
    (net (code "160") (name "unconnected-(C-Pad41)") (class "Default")
      (node (ref "C") (pin "41") (pinfunction "41_41") (pintype "passive"))
    )
    (net (code "161") (name "unconnected-(C-Pad43)") (class "Default")
      (node (ref "C") (pin "43") (pinfunction "43_43") (pintype "passive"))
    )
    (net (code "162") (name "unconnected-(C-Pad45)") (class "Default")
      (node (ref "C") (pin "45") (pinfunction "45_45") (pintype "passive"))
    )
    (net (code "163") (name "unconnected-(C-Pad47)") (class "Default")
      (node (ref "C") (pin "47") (pinfunction "47_47") (pintype "passive"))
    )
    (net (code "164") (name "unconnected-(C-Pad49)") (class "Default")
      (node (ref "C") (pin "49") (pinfunction "49_49") (pintype "passive"))
    )
    (net (code "165") (name "unconnected-(C-Pad51)") (class "Default")
      (node (ref "C") (pin "51") (pinfunction "51_51") (pintype "passive"))
    )
    (net (code "166") (name "unconnected-(C-Pad53)") (class "Default")
      (node (ref "C") (pin "53") (pinfunction "53_53") (pintype "passive"))
    )
    (net (code "167") (name "unconnected-(C-Pad55)") (class "Default")
      (node (ref "C") (pin "55") (pinfunction "55_55") (pintype "passive"))
    )
    (net (code "168") (name "unconnected-(C-Pad57)") (class "Default")
      (node (ref "C") (pin "57") (pinfunction "57_57") (pintype "passive"))
    )
    (net (code "169") (name "unconnected-(C-Pad59)") (class "Default")
      (node (ref "C") (pin "59") (pinfunction "59_59") (pintype "passive"))
    )
    (net (code "170") (name "unconnected-(M1-Pad5)") (class "Default")
      (node (ref "M1") (pin "5") (pinfunction "5_5") (pintype "passive"))
    )
    (net (code "171") (name "unconnected-(M1-Pad6)") (class "Default")
      (node (ref "M1") (pin "6") (pinfunction "6_6") (pintype "passive"))
    )
    (net (code "172") (name "unconnected-(M2-Pad5)") (class "Default")
      (node (ref "M2") (pin "5") (pinfunction "5_5") (pintype "passive"))
    )
    (net (code "173") (name "unconnected-(M2-Pad6)") (class "Default")
      (node (ref "M2") (pin "6") (pinfunction "6_6") (pintype "passive"))
    )
    (net (code "174") (name "unconnected-(M3-PadMP1)") (class "Default")
      (node (ref "M3") (pin "MP1") (pinfunction "MP1_MP1") (pintype "passive"))
    )
    (net (code "175") (name "unconnected-(M3-PadMP2)") (class "Default")
      (node (ref "M3") (pin "MP2") (pinfunction "MP2_MP2") (pintype "passive"))
    )
  )
)
